# LM2587SCH.net
KiCad netlist of a schematic drawn in Altium Designer
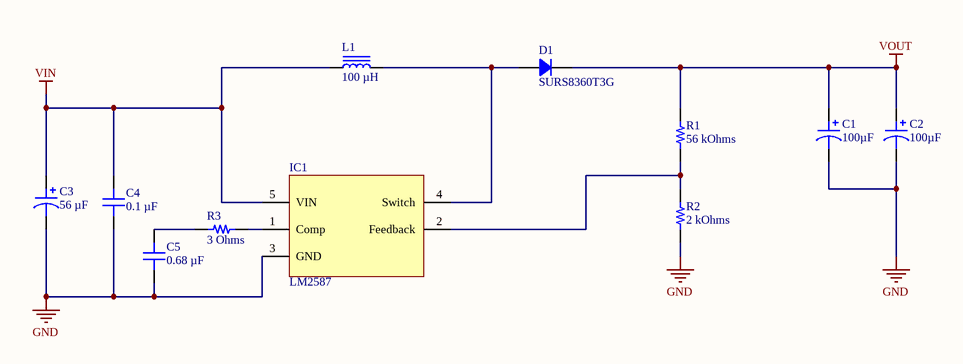
[diagram p0: LM2587SCH.SchDoc]

(export (version "E")
  (design (tool "Eeschema 10.0.6"))
  (components
    (comp (ref "C1")
      (value "100µF")
      (footprint "CAP ALSMD 8.3MM H10.5MM")
      (description "CAP ALUM 100UF 20% 50V SMD")
      (fields
        (field (name "PART NUMBER") "EEE-FK1H101P")
        (field (name "MANUFACTURER") "Panasonic Electronic Components")
      )
      (libsource (lib "Celestial Altium Library - altium_library") (part "Polarised Capacitor"))
    )
    (comp (ref "C2")
      (value "100µF")
      (footprint "CAP ALSMD 8.3MM H10.5MM")
      (description "CAP ALUM 100UF 20% 50V SMD")
      (fields
        (field (name "PART NUMBER") "EEE-FK1H101P")
        (field (name "MANUFACTURER") "Panasonic Electronic Components")
      )
      (libsource (lib "Celestial Altium Library - altium_library") (part "Polarised Capacitor"))
    )
    (comp (ref "C3")
      (value "56 µF")
      (footprint "CAP ALSMD 6.6MM H7.7MM")
      (description "CAP ALUM 56UF 20% 35V SMD")
      (fields (field (name "PART NUMBER") "UUD1V560MCL1GS") (field (name "MANUFACTURER") "Nichicon"))
      (libsource (lib "Celestial Altium Library - altium_library") (part "Polarised Capacitor"))
    )
    (comp (ref "C4")
      (value "0.1 µF")
      (footprint "CAP 0805_2012")
      (description "CAP CER 0.1UF 50V X7R 0805")
      (fields
        (field (name "PART NUMBER") "0805B104J500CT")
        (field (name "MANUFACTURER") "Walsin Technology Corporation")
      )
      (libsource (lib "Celestial Altium Library - altium_library") (part "Capacitor"))
    )
    (comp (ref "C5")
      (value "0.68 µF")
      (footprint "CAP 0805_2012")
      (description "CAP CER 0.68UF 50V X7R 0805")
      (fields (field (name "PART NUMBER") "C0805C684K5RACAUTO7210") (field (name "MANUFACTURER") "KEMET"))
      (libsource (lib "Celestial Altium Library - altium_library") (part "Capacitor"))
    )
    (comp (ref "D1")
      (value "SURS8360T3G")
      (footprint "DO214AB SMC")
      (description "DIODE GEN PURP 600V 3A SMC")
      (fields (field (name "MANUFACTURER") "ON Semiconductor"))
      (libsource (lib "Celestial Altium Library - altium_library") (part "Diode"))
    )
    (comp (ref "IC1")
      (value "LM2587")
      (footprint "LM2596:LM2596")
      (description "Boost Converter")
      (libsource (lib "LM2596") (part "LM2587"))
    )
    (comp (ref "L1")
      (value "100 µH")
      (footprint "7447070_inductor")
      (description "FIXED IND 100UH 2.1A 150MOHM SMD")
      (fields (field (name "PART NUMBER") "SRR1280-101M") (field (name "MANUFACTURER") "Bourns Inc."))
      (libsource (lib "Celestial Altium Library - altium_library") (part "Inductor"))
    )
    (comp (ref "R1")
      (value "56 kOhms")
      (footprint "RES 0805_2012")
      (description "RES 56K OHM 1% 1/8W 0805")
      (fields
        (field (name "PART NUMBER") "RMCF0805FT56K0")
        (field (name "MANUFACTURER") "Stackpole Electronics Inc")
      )
      (libsource (lib "Celestial Altium Library - altium_library") (part "Resistor"))
    )
    (comp (ref "R2")
      (value "2 kOhms")
      (footprint "RES 0805_2012")
      (description "RES SMD 2K OHM 1% 0.4W 0805")
      (fields (field (name "PART NUMBER") "RCS08052K00FKEA") (field (name "MANUFACTURER") "Vishay Dale"))
      (libsource (lib "Celestial Altium Library - altium_library") (part "Resistor"))
    )
    (comp (ref "R3")
      (value "3 Ohms")
      (footprint "RES 0805_2012")
      (description "RES SMD 3 OHM 1% 1/3W 0805")
      (fields
        (field (name "PART NUMBER") "ERJ-6BQF3R0V")
        (field (name "MANUFACTURER") "Panasonic Electronic Components")
      )
      (libsource (lib "Celestial Altium Library - altium_library") (part "Resistor"))
    )
  )
  (nets
    (net (code "1") (name "GND") (class "Default")
      (node (ref "C1") (pin "2") (pinfunction "2_2") (pintype "passive"))
      (node (ref "C2") (pin "2") (pinfunction "2_2") (pintype "passive"))
      (node (ref "C3") (pin "2") (pinfunction "2_2") (pintype "passive"))
      (node (ref "C4") (pin "1") (pinfunction "1_1") (pintype "passive"))
      (node (ref "C5") (pin "1") (pinfunction "1_1") (pintype "passive"))
      (node (ref "IC1") (pin "3") (pinfunction "GND_3") (pintype "passive"))
      (node (ref "R2") (pin "1") (pinfunction "1_1") (pintype "passive"))
    )
    (net (code "2") (name "Net-(C5-Pad2)") (class "Default")
      (node (ref "C5") (pin "2") (pinfunction "2_2") (pintype "passive"))
      (node (ref "R3") (pin "1") (pinfunction "1_1") (pintype "passive"))
    )
    (net (code "3") (name "Net-(IC1-Comp)") (class "Default")
      (node (ref "IC1") (pin "1") (pinfunction "Comp_1") (pintype "passive"))
      (node (ref "R3") (pin "2") (pinfunction "2_2") (pintype "passive"))
    )
    (net (code "4") (name "Net-(IC1-Feedback)") (class "Default")
      (node (ref "IC1") (pin "2") (pinfunction "Feedback_2") (pintype "passive"))
      (node (ref "R1") (pin "1") (pinfunction "1_1") (pintype "passive"))
      (node (ref "R2") (pin "2") (pinfunction "2_2") (pintype "passive"))
    )
    (net (code "5") (name "Net-(IC1-Switch)") (class "Default")
      (node (ref "D1") (pin "1") (pinfunction "1_1") (pintype "passive"))
      (node (ref "IC1") (pin "4") (pinfunction "Switch_4") (pintype "passive"))
      (node (ref "L1") (pin "2") (pinfunction "2_2") (pintype "passive"))
    )
    (net (code "6") (name "VIN") (class "Default")
      (node (ref "C3") (pin "1") (pinfunction "1_1") (pintype "passive"))
      (node (ref "C4") (pin "2") (pinfunction "2_2") (pintype "passive"))
      (node (ref "IC1") (pin "5") (pinfunction "VIN_5") (pintype "passive"))
      (node (ref "L1") (pin "1") (pinfunction "1_1") (pintype "passive"))
    )
    (net (code "7") (name "VOUT") (class "Default")
      (node (ref "C1") (pin "1") (pinfunction "1_1") (pintype "passive"))
      (node (ref "C2") (pin "1") (pinfunction "1_1") (pintype "passive"))
      (node (ref "D1") (pin "2") (pinfunction "2_2") (pintype "passive"))
      (node (ref "R1") (pin "2") (pinfunction "2_2") (pintype "passive"))
    )
  )
)
